# Program-Counter.net
KiCad netlist of a schematic drawn in EAGLE
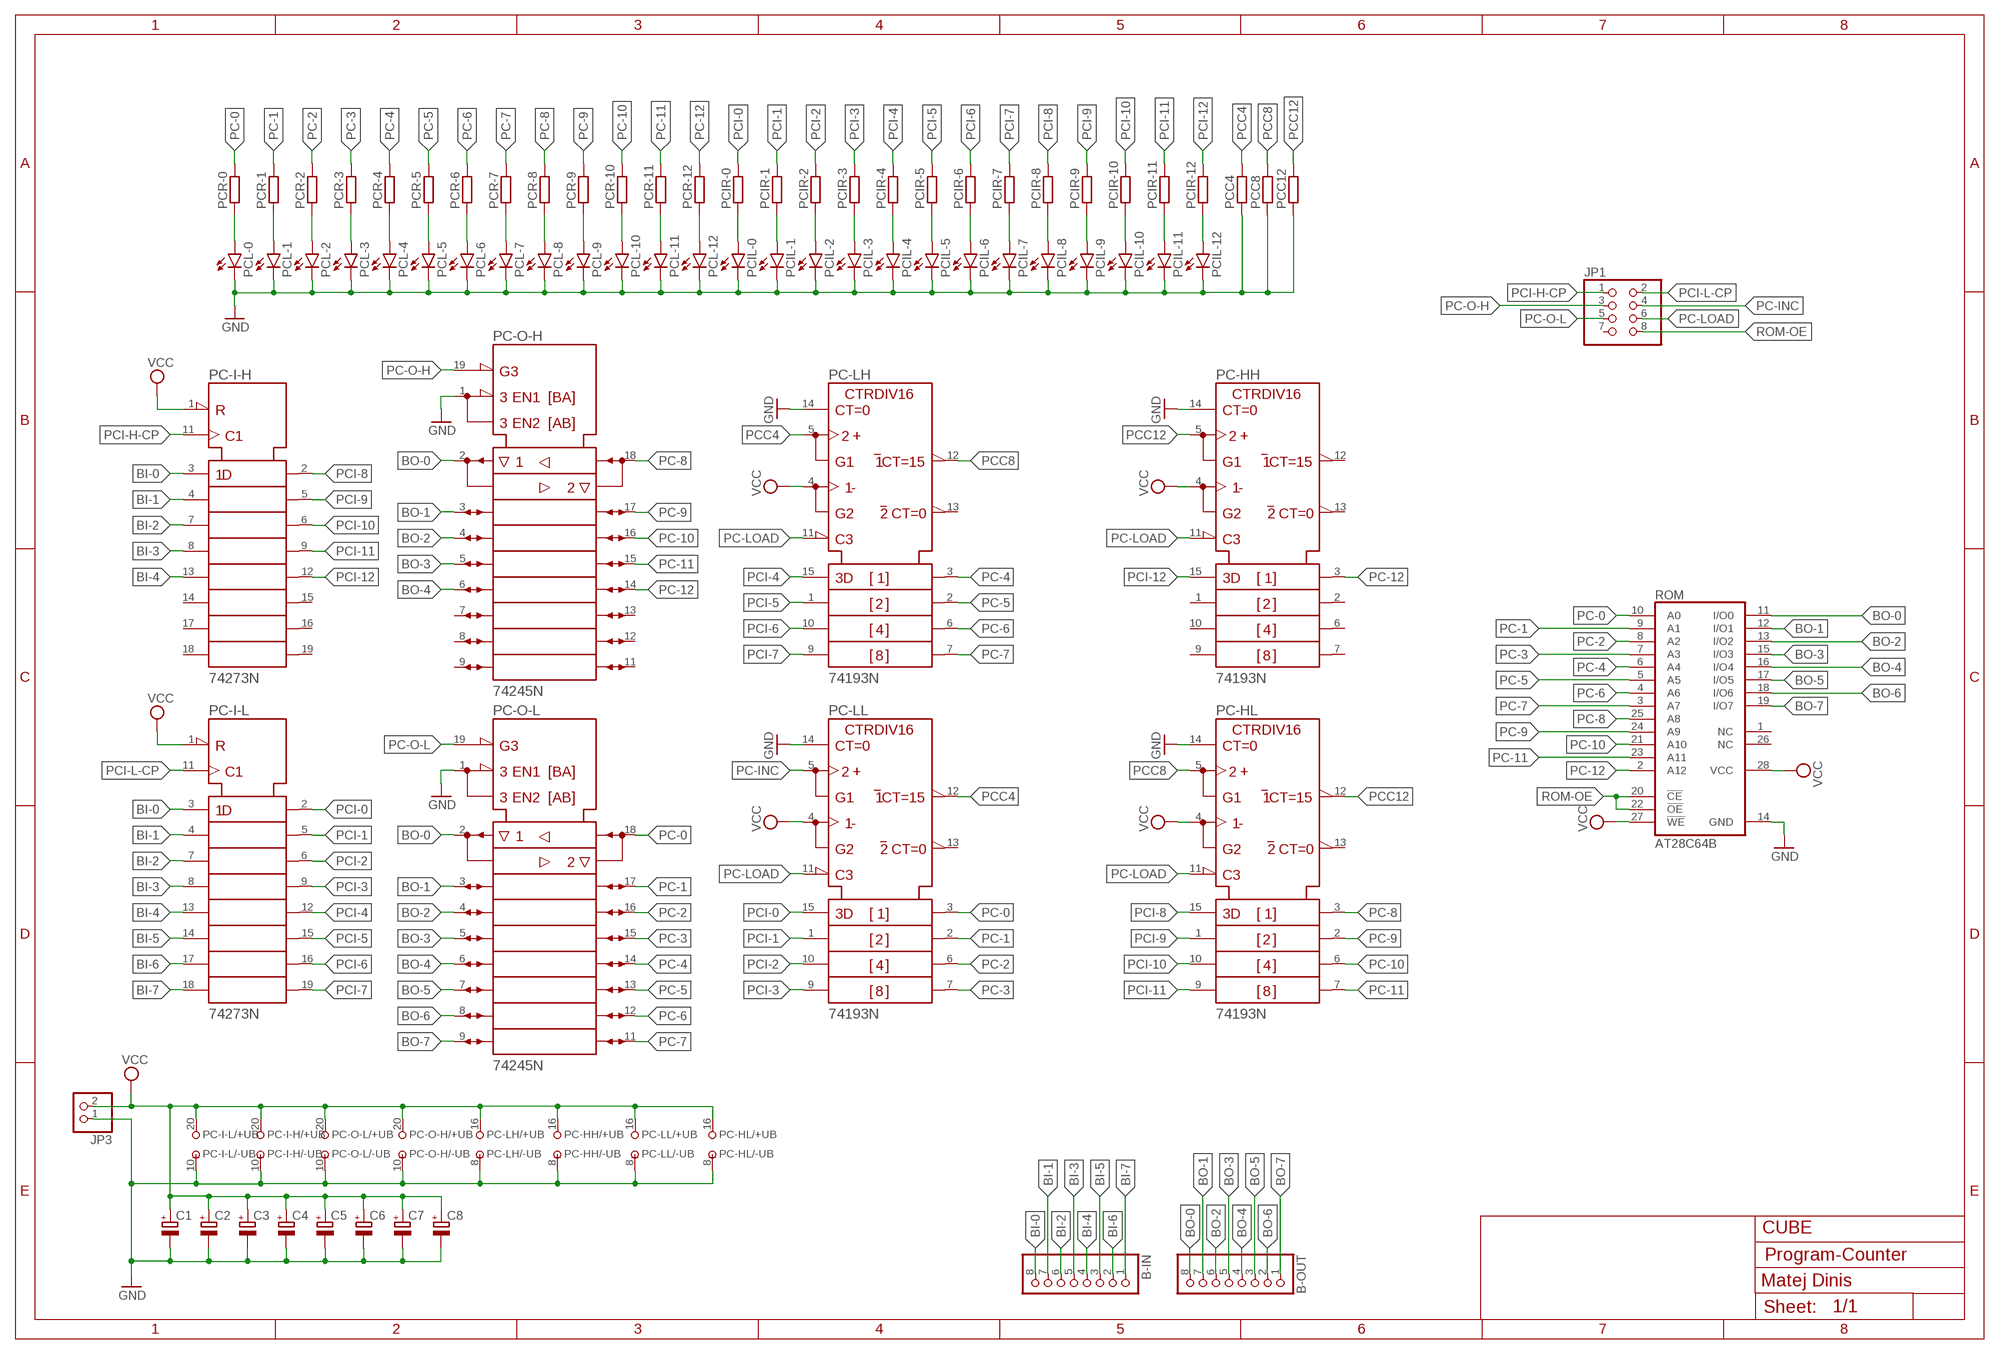
[diagram p0: schematic, sheet 1]

(export (version "E")
  (design (tool "Eeschema 10.0.6"))
  (components
    (comp (ref "B-IN")
      (value "PINHD-1X8")
      (footprint "eagle-import:1X08")
      (libsource (lib "eagle-import") (part "PINHD-1X8"))
    )
    (comp (ref "B-OUT")
      (value "PINHD-1X8")
      (footprint "eagle-import:1X08")
      (libsource (lib "eagle-import") (part "PINHD-1X8"))
    )
    (comp (ref "C1")
      (value "CPOL-EUE3.5-8")
      (footprint "eagle-import:E3,5-8")
      (libsource (lib "eagle-import") (part "CPOL-EUE3.5-8"))
    )
    (comp (ref "C2")
      (value "CPOL-EUE3.5-8")
      (footprint "eagle-import:E3,5-8")
      (libsource (lib "eagle-import") (part "CPOL-EUE3.5-8"))
    )
    (comp (ref "C3")
      (value "CPOL-EUE3.5-8")
      (footprint "eagle-import:E3,5-8")
      (libsource (lib "eagle-import") (part "CPOL-EUE3.5-8"))
    )
    (comp (ref "C4")
      (value "CPOL-EUE3.5-8")
      (footprint "eagle-import:E3,5-8")
      (libsource (lib "eagle-import") (part "CPOL-EUE3.5-8"))
    )
    (comp (ref "C5")
      (value "CPOL-EUE3.5-8")
      (footprint "eagle-import:E3,5-8")
      (libsource (lib "eagle-import") (part "CPOL-EUE3.5-8"))
    )
    (comp (ref "C6")
      (value "CPOL-EUE3.5-8")
      (footprint "eagle-import:E3,5-8")
      (libsource (lib "eagle-import") (part "CPOL-EUE3.5-8"))
    )
    (comp (ref "C7")
      (value "CPOL-EUE3.5-8")
      (footprint "eagle-import:E3,5-8")
      (libsource (lib "eagle-import") (part "CPOL-EUE3.5-8"))
    )
    (comp (ref "C8")
      (value "CPOL-EUE3.5-8")
      (footprint "eagle-import:E3,5-8")
      (libsource (lib "eagle-import") (part "CPOL-EUE3.5-8"))
    )
    (comp (ref "JP1")
      (value "PINHD-2X4")
      (footprint "eagle-import:2X04")
      (libsource (lib "eagle-import") (part "PINHD-2X4"))
    )
    (comp (ref "JP3")
      (value "PINHD-1X2")
      (footprint "eagle-import:1X02")
      (libsource (lib "eagle-import") (part "PINHD-1X2"))
    )
    (comp (ref "PC-HH")
      (value "74193N")
      (footprint "eagle-import:DIL16")
      (libsource (lib "eagle-import") (part "74193N"))
    )
    (comp (ref "PC-HL")
      (value "74193N")
      (footprint "eagle-import:DIL16")
      (libsource (lib "eagle-import") (part "74193N"))
    )
    (comp (ref "PC-I-H")
      (value "74273N")
      (footprint "eagle-import:DIL20")
      (libsource (lib "eagle-import") (part "74273N"))
    )
    (comp (ref "PC-I-L")
      (value "74273N")
      (footprint "eagle-import:DIL20")
      (libsource (lib "eagle-import") (part "74273N"))
    )
    (comp (ref "PC-LH")
      (value "74193N")
      (footprint "eagle-import:DIL16")
      (libsource (lib "eagle-import") (part "74193N"))
    )
    (comp (ref "PC-LL")
      (value "74193N")
      (footprint "eagle-import:DIL16")
      (libsource (lib "eagle-import") (part "74193N"))
    )
    (comp (ref "PC-O-H")
      (value "74245N")
      (footprint "eagle-import:DIL20")
      (libsource (lib "eagle-import") (part "74245N"))
    )
    (comp (ref "PC-O-L")
      (value "74245N")
      (footprint "eagle-import:DIL20")
      (libsource (lib "eagle-import") (part "74245N"))
    )
    (comp (ref "PCC4")
      (value "R-EU_0207/10")
      (footprint "eagle-import:0207_10")
      (libsource (lib "eagle-import") (part "R-EU_0207/10"))
    )
    (comp (ref "PCC8")
      (value "R-EU_0207/10")
      (footprint "eagle-import:0207_10")
      (libsource (lib "eagle-import") (part "R-EU_0207/10"))
    )
    (comp (ref "PCC12")
      (value "R-EU_0207/10")
      (footprint "eagle-import:0207_10")
      (libsource (lib "eagle-import") (part "R-EU_0207/10"))
    )
    (comp (ref "PCIL-0")
      (value "LED5MM")
      (footprint "eagle-import:LED5MM")
      (libsource (lib "eagle-import") (part "LED5MM"))
    )
    (comp (ref "PCIL-1")
      (value "LED5MM")
      (footprint "eagle-import:LED5MM")
      (libsource (lib "eagle-import") (part "LED5MM"))
    )
    (comp (ref "PCIL-2")
      (value "LED5MM")
      (footprint "eagle-import:LED5MM")
      (libsource (lib "eagle-import") (part "LED5MM"))
    )
    (comp (ref "PCIL-3")
      (value "LED5MM")
      (footprint "eagle-import:LED5MM")
      (libsource (lib "eagle-import") (part "LED5MM"))
    )
    (comp (ref "PCIL-4")
      (value "LED5MM")
      (footprint "eagle-import:LED5MM")
      (libsource (lib "eagle-import") (part "LED5MM"))
    )
    (comp (ref "PCIL-5")
      (value "LED5MM")
      (footprint "eagle-import:LED5MM")
      (libsource (lib "eagle-import") (part "LED5MM"))
    )
    (comp (ref "PCIL-6")
      (value "LED5MM")
      (footprint "eagle-import:LED5MM")
      (libsource (lib "eagle-import") (part "LED5MM"))
    )
    (comp (ref "PCIL-7")
      (value "LED5MM")
      (footprint "eagle-import:LED5MM")
      (libsource (lib "eagle-import") (part "LED5MM"))
    )
    (comp (ref "PCIL-8")
      (value "LED5MM")
      (footprint "eagle-import:LED5MM")
      (libsource (lib "eagle-import") (part "LED5MM"))
    )
    (comp (ref "PCIL-9")
      (value "LED5MM")
      (footprint "eagle-import:LED5MM")
      (libsource (lib "eagle-import") (part "LED5MM"))
    )
    (comp (ref "PCIL-10")
      (value "LED5MM")
      (footprint "eagle-import:LED5MM")
      (libsource (lib "eagle-import") (part "LED5MM"))
    )
    (comp (ref "PCIL-11")
      (value "LED5MM")
      (footprint "eagle-import:LED5MM")
      (libsource (lib "eagle-import") (part "LED5MM"))
    )
    (comp (ref "PCIL-12")
      (value "LED5MM")
      (footprint "eagle-import:LED5MM")
      (libsource (lib "eagle-import") (part "LED5MM"))
    )
    (comp (ref "PCIR-0")
      (value "R-EU_0207/10")
      (footprint "eagle-import:0207_10")
      (libsource (lib "eagle-import") (part "R-EU_0207/10"))
    )
    (comp (ref "PCIR-1")
      (value "R-EU_0207/10")
      (footprint "eagle-import:0207_10")
      (libsource (lib "eagle-import") (part "R-EU_0207/10"))
    )
    (comp (ref "PCIR-2")
      (value "R-EU_0207/10")
      (footprint "eagle-import:0207_10")
      (libsource (lib "eagle-import") (part "R-EU_0207/10"))
    )
    (comp (ref "PCIR-3")
      (value "R-EU_0207/10")
      (footprint "eagle-import:0207_10")
      (libsource (lib "eagle-import") (part "R-EU_0207/10"))
    )
    (comp (ref "PCIR-4")
      (value "R-EU_0207/10")
      (footprint "eagle-import:0207_10")
      (libsource (lib "eagle-import") (part "R-EU_0207/10"))
    )
    (comp (ref "PCIR-5")
      (value "R-EU_0207/10")
      (footprint "eagle-import:0207_10")
      (libsource (lib "eagle-import") (part "R-EU_0207/10"))
    )
    (comp (ref "PCIR-6")
      (value "R-EU_0207/10")
      (footprint "eagle-import:0207_10")
      (libsource (lib "eagle-import") (part "R-EU_0207/10"))
    )
    (comp (ref "PCIR-7")
      (value "R-EU_0207/10")
      (footprint "eagle-import:0207_10")
      (libsource (lib "eagle-import") (part "R-EU_0207/10"))
    )
    (comp (ref "PCIR-8")
      (value "R-EU_0207/10")
      (footprint "eagle-import:0207_10")
      (libsource (lib "eagle-import") (part "R-EU_0207/10"))
    )
    (comp (ref "PCIR-9")
      (value "R-EU_0207/10")
      (footprint "eagle-import:0207_10")
      (libsource (lib "eagle-import") (part "R-EU_0207/10"))
    )
    (comp (ref "PCIR-10")
      (value "R-EU_0207/10")
      (footprint "eagle-import:0207_10")
      (libsource (lib "eagle-import") (part "R-EU_0207/10"))
    )
    (comp (ref "PCIR-11")
      (value "R-EU_0207/10")
      (footprint "eagle-import:0207_10")
      (libsource (lib "eagle-import") (part "R-EU_0207/10"))
    )
    (comp (ref "PCIR-12")
      (value "R-EU_0207/10")
      (footprint "eagle-import:0207_10")
      (libsource (lib "eagle-import") (part "R-EU_0207/10"))
    )
    (comp (ref "PCL-0")
      (value "LED5MM")
      (footprint "eagle-import:LED5MM")
      (libsource (lib "eagle-import") (part "LED5MM"))
    )
    (comp (ref "PCL-1")
      (value "LED5MM")
      (footprint "eagle-import:LED5MM")
      (libsource (lib "eagle-import") (part "LED5MM"))
    )
    (comp (ref "PCL-2")
      (value "LED5MM")
      (footprint "eagle-import:LED5MM")
      (libsource (lib "eagle-import") (part "LED5MM"))
    )
    (comp (ref "PCL-3")
      (value "LED5MM")
      (footprint "eagle-import:LED5MM")
      (libsource (lib "eagle-import") (part "LED5MM"))
    )
    (comp (ref "PCL-4")
      (value "LED5MM")
      (footprint "eagle-import:LED5MM")
      (libsource (lib "eagle-import") (part "LED5MM"))
    )
    (comp (ref "PCL-5")
      (value "LED5MM")
      (footprint "eagle-import:LED5MM")
      (libsource (lib "eagle-import") (part "LED5MM"))
    )
    (comp (ref "PCL-6")
      (value "LED5MM")
      (footprint "eagle-import:LED5MM")
      (libsource (lib "eagle-import") (part "LED5MM"))
    )
    (comp (ref "PCL-7")
      (value "LED5MM")
      (footprint "eagle-import:LED5MM")
      (libsource (lib "eagle-import") (part "LED5MM"))
    )
    (comp (ref "PCL-8")
      (value "LED5MM")
      (footprint "eagle-import:LED5MM")
      (libsource (lib "eagle-import") (part "LED5MM"))
    )
    (comp (ref "PCL-9")
      (value "LED5MM")
      (footprint "eagle-import:LED5MM")
      (libsource (lib "eagle-import") (part "LED5MM"))
    )
    (comp (ref "PCL-10")
      (value "LED5MM")
      (footprint "eagle-import:LED5MM")
      (libsource (lib "eagle-import") (part "LED5MM"))
    )
    (comp (ref "PCL-11")
      (value "LED5MM")
      (footprint "eagle-import:LED5MM")
      (libsource (lib "eagle-import") (part "LED5MM"))
    )
    (comp (ref "PCL-12")
      (value "LED5MM")
      (footprint "eagle-import:LED5MM")
      (libsource (lib "eagle-import") (part "LED5MM"))
    )
    (comp (ref "PCR-0")
      (value "R-EU_0207/10")
      (footprint "eagle-import:0207_10")
      (libsource (lib "eagle-import") (part "R-EU_0207/10"))
    )
    (comp (ref "PCR-1")
      (value "R-EU_0207/10")
      (footprint "eagle-import:0207_10")
      (libsource (lib "eagle-import") (part "R-EU_0207/10"))
    )
    (comp (ref "PCR-2")
      (value "R-EU_0207/10")
      (footprint "eagle-import:0207_10")
      (libsource (lib "eagle-import") (part "R-EU_0207/10"))
    )
    (comp (ref "PCR-3")
      (value "R-EU_0207/10")
      (footprint "eagle-import:0207_10")
      (libsource (lib "eagle-import") (part "R-EU_0207/10"))
    )
    (comp (ref "PCR-4")
      (value "R-EU_0207/10")
      (footprint "eagle-import:0207_10")
      (libsource (lib "eagle-import") (part "R-EU_0207/10"))
    )
    (comp (ref "PCR-5")
      (value "R-EU_0207/10")
      (footprint "eagle-import:0207_10")
      (libsource (lib "eagle-import") (part "R-EU_0207/10"))
    )
    (comp (ref "PCR-6")
      (value "R-EU_0207/10")
      (footprint "eagle-import:0207_10")
      (libsource (lib "eagle-import") (part "R-EU_0207/10"))
    )
    (comp (ref "PCR-7")
      (value "R-EU_0207/10")
      (footprint "eagle-import:0207_10")
      (libsource (lib "eagle-import") (part "R-EU_0207/10"))
    )
    (comp (ref "PCR-8")
      (value "R-EU_0207/10")
      (footprint "eagle-import:0207_10")
      (libsource (lib "eagle-import") (part "R-EU_0207/10"))
    )
    (comp (ref "PCR-9")
      (value "R-EU_0207/10")
      (footprint "eagle-import:0207_10")
      (libsource (lib "eagle-import") (part "R-EU_0207/10"))
    )
    (comp (ref "PCR-10")
      (value "R-EU_0207/10")
      (footprint "eagle-import:0207_10")
      (libsource (lib "eagle-import") (part "R-EU_0207/10"))
    )
    (comp (ref "PCR-11")
      (value "R-EU_0207/10")
      (footprint "eagle-import:0207_10")
      (libsource (lib "eagle-import") (part "R-EU_0207/10"))
    )
    (comp (ref "PCR-12")
      (value "R-EU_0207/10")
      (footprint "eagle-import:0207_10")
      (libsource (lib "eagle-import") (part "R-EU_0207/10"))
    )
    (comp (ref "ROM")
      (value "AT28C64B")
      (footprint "eagle-import:DIL28-6")
      (fields (field (name "MPN") "AT28C64B-15PU"))
      (libsource (lib "eagle-import") (part "28C64C"))
    )
  )
  (nets
    (net (code "1") (name "BI-0") (class "Default")
      (node (ref "B-IN") (pin "8") (pinfunction "8_8") (pintype "passive"))
      (node (ref "PC-I-H") (pin "3") (pinfunction "1D_3") (pintype "input"))
      (node (ref "PC-I-L") (pin "3") (pinfunction "1D_3") (pintype "input"))
    )
    (net (code "2") (name "BI-1") (class "Default")
      (node (ref "B-IN") (pin "7") (pinfunction "7_7") (pintype "passive"))
      (node (ref "PC-I-H") (pin "4") (pinfunction "2D_4") (pintype "input"))
      (node (ref "PC-I-L") (pin "4") (pinfunction "2D_4") (pintype "input"))
    )
    (net (code "3") (name "BI-2") (class "Default")
      (node (ref "B-IN") (pin "6") (pinfunction "6_6") (pintype "passive"))
      (node (ref "PC-I-H") (pin "7") (pinfunction "3D_7") (pintype "input"))
      (node (ref "PC-I-L") (pin "7") (pinfunction "3D_7") (pintype "input"))
    )
    (net (code "4") (name "BI-3") (class "Default")
      (node (ref "B-IN") (pin "5") (pinfunction "5_5") (pintype "passive"))
      (node (ref "PC-I-H") (pin "8") (pinfunction "4D_8") (pintype "input"))
      (node (ref "PC-I-L") (pin "8") (pinfunction "4D_8") (pintype "input"))
    )
    (net (code "5") (name "BI-4") (class "Default")
      (node (ref "B-IN") (pin "4") (pinfunction "4_4") (pintype "passive"))
      (node (ref "PC-I-H") (pin "13") (pinfunction "5D_13") (pintype "input"))
      (node (ref "PC-I-L") (pin "13") (pinfunction "5D_13") (pintype "input"))
    )
    (net (code "6") (name "BI-5") (class "Default")
      (node (ref "B-IN") (pin "3") (pinfunction "3_3") (pintype "passive"))
      (node (ref "PC-I-L") (pin "14") (pinfunction "6D_14") (pintype "input"))
    )
    (net (code "7") (name "BI-6") (class "Default")
      (node (ref "B-IN") (pin "2") (pinfunction "2_2") (pintype "passive"))
      (node (ref "PC-I-L") (pin "17") (pinfunction "7D_17") (pintype "input"))
    )
    (net (code "8") (name "BI-7") (class "Default")
      (node (ref "B-IN") (pin "1") (pinfunction "1_1") (pintype "passive"))
      (node (ref "PC-I-L") (pin "18") (pinfunction "8D_18") (pintype "input"))
    )
    (net (code "9") (name "BO-0") (class "Default")
      (node (ref "B-OUT") (pin "8") (pinfunction "8_8") (pintype "passive"))
      (node (ref "PC-O-H") (pin "2") (pinfunction "A1_2") (pintype "bidirectional"))
      (node (ref "PC-O-L") (pin "2") (pinfunction "A1_2") (pintype "bidirectional"))
      (node (ref "ROM") (pin "11") (pinfunction "I/O0_11") (pintype "bidirectional"))
    )
    (net (code "10") (name "BO-1") (class "Default")
      (node (ref "B-OUT") (pin "7") (pinfunction "7_7") (pintype "passive"))
      (node (ref "PC-O-H") (pin "3") (pinfunction "A2_3") (pintype "bidirectional"))
      (node (ref "PC-O-L") (pin "3") (pinfunction "A2_3") (pintype "bidirectional"))
      (node (ref "ROM") (pin "12") (pinfunction "I/O1_12") (pintype "bidirectional"))
    )
    (net (code "11") (name "BO-2") (class "Default")
      (node (ref "B-OUT") (pin "6") (pinfunction "6_6") (pintype "passive"))
      (node (ref "PC-O-H") (pin "4") (pinfunction "A3_4") (pintype "bidirectional"))
      (node (ref "PC-O-L") (pin "4") (pinfunction "A3_4") (pintype "bidirectional"))
      (node (ref "ROM") (pin "13") (pinfunction "I/O2_13") (pintype "bidirectional"))
    )
    (net (code "12") (name "BO-3") (class "Default")
      (node (ref "B-OUT") (pin "5") (pinfunction "5_5") (pintype "passive"))
      (node (ref "PC-O-H") (pin "5") (pinfunction "A4_5") (pintype "bidirectional"))
      (node (ref "PC-O-L") (pin "5") (pinfunction "A4_5") (pintype "bidirectional"))
      (node (ref "ROM") (pin "15") (pinfunction "I/O3_15") (pintype "bidirectional"))
    )
    (net (code "13") (name "BO-4") (class "Default")
      (node (ref "B-OUT") (pin "4") (pinfunction "4_4") (pintype "passive"))
      (node (ref "PC-O-H") (pin "6") (pinfunction "A5_6") (pintype "bidirectional"))
      (node (ref "PC-O-L") (pin "6") (pinfunction "A5_6") (pintype "bidirectional"))
      (node (ref "ROM") (pin "16") (pinfunction "I/O4_16") (pintype "bidirectional"))
    )
    (net (code "14") (name "BO-5") (class "Default")
      (node (ref "B-OUT") (pin "3") (pinfunction "3_3") (pintype "passive"))
      (node (ref "PC-O-L") (pin "7") (pinfunction "A6_7") (pintype "bidirectional"))
      (node (ref "ROM") (pin "17") (pinfunction "I/O5_17") (pintype "bidirectional"))
    )
    (net (code "15") (name "BO-6") (class "Default")
      (node (ref "B-OUT") (pin "2") (pinfunction "2_2") (pintype "passive"))
      (node (ref "PC-O-L") (pin "8") (pinfunction "A7_8") (pintype "bidirectional"))
      (node (ref "ROM") (pin "18") (pinfunction "I/O6_18") (pintype "bidirectional"))
    )
    (net (code "16") (name "BO-7") (class "Default")
      (node (ref "B-OUT") (pin "1") (pinfunction "1_1") (pintype "passive"))
      (node (ref "PC-O-L") (pin "9") (pinfunction "A8_9") (pintype "bidirectional"))
      (node (ref "ROM") (pin "19") (pinfunction "I/O7_19") (pintype "bidirectional"))
    )
    (net (code "17") (name "GND") (class "Default")
      (node (ref "C1") (pin "-") (pinfunction "-_-") (pintype "passive"))
      (node (ref "C2") (pin "-") (pinfunction "-_-") (pintype "passive"))
      (node (ref "C3") (pin "-") (pinfunction "-_-") (pintype "passive"))
      (node (ref "C4") (pin "-") (pinfunction "-_-") (pintype "passive"))
      (node (ref "C5") (pin "-") (pinfunction "-_-") (pintype "passive"))
      (node (ref "C6") (pin "-") (pinfunction "-_-") (pintype "passive"))
      (node (ref "C7") (pin "-") (pinfunction "-_-") (pintype "passive"))
      (node (ref "C8") (pin "-") (pinfunction "-_-") (pintype "passive"))
      (node (ref "JP3") (pin "1") (pinfunction "1_1") (pintype "passive"))
      (node (ref "PC-HH") (pin "14") (pinfunction "CLR_14") (pintype "input"))
      (node (ref "PC-HH") (pin "8") (pinfunction "-UB_8") (pintype "power_in"))
      (node (ref "PC-HL") (pin "14") (pinfunction "CLR_14") (pintype "input"))
      (node (ref "PC-HL") (pin "8") (pinfunction "-UB_8") (pintype "power_in"))
      (node (ref "PC-I-H") (pin "10") (pinfunction "-UB_10") (pintype "power_in"))
      (node (ref "PC-I-L") (pin "10") (pinfunction "-UB_10") (pintype "power_in"))
      (node (ref "PC-LH") (pin "14") (pinfunction "CLR_14") (pintype "input"))
      (node (ref "PC-LH") (pin "8") (pinfunction "-UB_8") (pintype "power_in"))
      (node (ref "PC-LL") (pin "14") (pinfunction "CLR_14") (pintype "input"))
      (node (ref "PC-LL") (pin "8") (pinfunction "-UB_8") (pintype "power_in"))
      (node (ref "PC-O-H") (pin "1") (pinfunction "DIR_1") (pintype "input"))
      (node (ref "PC-O-H") (pin "10") (pinfunction "-UB_10") (pintype "power_in"))
      (node (ref "PC-O-L") (pin "1") (pinfunction "DIR_1") (pintype "input"))
      (node (ref "PC-O-L") (pin "10") (pinfunction "-UB_10") (pintype "power_in"))
      (node (ref "PCC12") (pin "1") (pinfunction "1_1") (pintype "passive"))
      (node (ref "PCC4") (pin "1") (pinfunction "1_1") (pintype "passive"))
      (node (ref "PCC8") (pin "1") (pinfunction "1_1") (pintype "passive"))
      (node (ref "PCIL-0") (pin "K") (pinfunction "C_K") (pintype "passive"))
      (node (ref "PCIL-1") (pin "K") (pinfunction "C_K") (pintype "passive"))
      (node (ref "PCIL-10") (pin "K") (pinfunction "C_K") (pintype "passive"))
      (node (ref "PCIL-11") (pin "K") (pinfunction "C_K") (pintype "passive"))
      (node (ref "PCIL-12") (pin "K") (pinfunction "C_K") (pintype "passive"))
      (node (ref "PCIL-2") (pin "K") (pinfunction "C_K") (pintype "passive"))
      (node (ref "PCIL-3") (pin "K") (pinfunction "C_K") (pintype "passive"))
      (node (ref "PCIL-4") (pin "K") (pinfunction "C_K") (pintype "passive"))
      (node (ref "PCIL-5") (pin "K") (pinfunction "C_K") (pintype "passive"))
      (node (ref "PCIL-6") (pin "K") (pinfunction "C_K") (pintype "passive"))
      (node (ref "PCIL-7") (pin "K") (pinfunction "C_K") (pintype "passive"))
      (node (ref "PCIL-8") (pin "K") (pinfunction "C_K") (pintype "passive"))
      (node (ref "PCIL-9") (pin "K") (pinfunction "C_K") (pintype "passive"))
      (node (ref "PCL-0") (pin "K") (pinfunction "C_K") (pintype "passive"))
      (node (ref "PCL-1") (pin "K") (pinfunction "C_K") (pintype "passive"))
      (node (ref "PCL-10") (pin "K") (pinfunction "C_K") (pintype "passive"))
      (node (ref "PCL-11") (pin "K") (pinfunction "C_K") (pintype "passive"))
      (node (ref "PCL-12") (pin "K") (pinfunction "C_K") (pintype "passive"))
      (node (ref "PCL-2") (pin "K") (pinfunction "C_K") (pintype "passive"))
      (node (ref "PCL-3") (pin "K") (pinfunction "C_K") (pintype "passive"))
      (node (ref "PCL-4") (pin "K") (pinfunction "C_K") (pintype "passive"))
      (node (ref "PCL-5") (pin "K") (pinfunction "C_K") (pintype "passive"))
      (node (ref "PCL-6") (pin "K") (pinfunction "C_K") (pintype "passive"))
      (node (ref "PCL-7") (pin "K") (pinfunction "C_K") (pintype "passive"))
      (node (ref "PCL-8") (pin "K") (pinfunction "C_K") (pintype "passive"))
      (node (ref "PCL-9") (pin "K") (pinfunction "C_K") (pintype "passive"))
      (node (ref "ROM") (pin "14") (pinfunction "GND_14") (pintype "power_in"))
    )
    (net (code "18") (name "Net-(PCIL-0-PadA)") (class "Default")
      (node (ref "PCIL-0") (pin "A") (pinfunction "A_A") (pintype "passive"))
      (node (ref "PCIR-0") (pin "1") (pinfunction "1_1") (pintype "passive"))
    )
    (net (code "19") (name "Net-(PCIL-1-PadA)") (class "Default")
      (node (ref "PCIL-1") (pin "A") (pinfunction "A_A") (pintype "passive"))
      (node (ref "PCIR-1") (pin "1") (pinfunction "1_1") (pintype "passive"))
    )
    (net (code "20") (name "Net-(PCIL-2-PadA)") (class "Default")
      (node (ref "PCIL-2") (pin "A") (pinfunction "A_A") (pintype "passive"))
      (node (ref "PCIR-2") (pin "1") (pinfunction "1_1") (pintype "passive"))
    )
    (net (code "21") (name "Net-(PCIL-3-PadA)") (class "Default")
      (node (ref "PCIL-3") (pin "A") (pinfunction "A_A") (pintype "passive"))
      (node (ref "PCIR-3") (pin "1") (pinfunction "1_1") (pintype "passive"))
    )
    (net (code "22") (name "Net-(PCIL-4-PadA)") (class "Default")
      (node (ref "PCIL-4") (pin "A") (pinfunction "A_A") (pintype "passive"))
      (node (ref "PCIR-4") (pin "1") (pinfunction "1_1") (pintype "passive"))
    )
    (net (code "23") (name "Net-(PCIL-5-PadA)") (class "Default")
      (node (ref "PCIL-5") (pin "A") (pinfunction "A_A") (pintype "passive"))
      (node (ref "PCIR-5") (pin "1") (pinfunction "1_1") (pintype "passive"))
    )
    (net (code "24") (name "Net-(PCIL-6-PadA)") (class "Default")
      (node (ref "PCIL-6") (pin "A") (pinfunction "A_A") (pintype "passive"))
      (node (ref "PCIR-6") (pin "1") (pinfunction "1_1") (pintype "passive"))
    )
    (net (code "25") (name "Net-(PCIL-7-PadA)") (class "Default")
      (node (ref "PCIL-7") (pin "A") (pinfunction "A_A") (pintype "passive"))
      (node (ref "PCIR-7") (pin "1") (pinfunction "1_1") (pintype "passive"))
    )
    (net (code "26") (name "Net-(PCIL-8-PadA)") (class "Default")
      (node (ref "PCIL-8") (pin "A") (pinfunction "A_A") (pintype "passive"))
      (node (ref "PCIR-8") (pin "1") (pinfunction "1_1") (pintype "passive"))
    )
    (net (code "27") (name "Net-(PCIL-9-PadA)") (class "Default")
      (node (ref "PCIL-9") (pin "A") (pinfunction "A_A") (pintype "passive"))
      (node (ref "PCIR-9") (pin "1") (pinfunction "1_1") (pintype "passive"))
    )
    (net (code "28") (name "Net-(PCIL-10-PadA)") (class "Default")
      (node (ref "PCIL-10") (pin "A") (pinfunction "A_A") (pintype "passive"))
      (node (ref "PCIR-10") (pin "1") (pinfunction "1_1") (pintype "passive"))
    )
    (net (code "29") (name "Net-(PCIL-11-PadA)") (class "Default")
      (node (ref "PCIL-11") (pin "A") (pinfunction "A_A") (pintype "passive"))
      (node (ref "PCIR-11") (pin "1") (pinfunction "1_1") (pintype "passive"))
    )
    (net (code "30") (name "Net-(PCIL-12-PadA)") (class "Default")
      (node (ref "PCIL-12") (pin "A") (pinfunction "A_A") (pintype "passive"))
      (node (ref "PCIR-12") (pin "1") (pinfunction "1_1") (pintype "passive"))
    )
    (net (code "31") (name "Net-(PCL-0-PadA)") (class "Default")
      (node (ref "PCL-0") (pin "A") (pinfunction "A_A") (pintype "passive"))
      (node (ref "PCR-0") (pin "1") (pinfunction "1_1") (pintype "passive"))
    )
    (net (code "32") (name "Net-(PCL-1-PadA)") (class "Default")
      (node (ref "PCL-1") (pin "A") (pinfunction "A_A") (pintype "passive"))
      (node (ref "PCR-1") (pin "1") (pinfunction "1_1") (pintype "passive"))
    )
    (net (code "33") (name "Net-(PCL-2-PadA)") (class "Default")
      (node (ref "PCL-2") (pin "A") (pinfunction "A_A") (pintype "passive"))
      (node (ref "PCR-2") (pin "1") (pinfunction "1_1") (pintype "passive"))
    )
    (net (code "34") (name "Net-(PCL-3-PadA)") (class "Default")
      (node (ref "PCL-3") (pin "A") (pinfunction "A_A") (pintype "passive"))
      (node (ref "PCR-3") (pin "1") (pinfunction "1_1") (pintype "passive"))
    )
    (net (code "35") (name "Net-(PCL-4-PadA)") (class "Default")
      (node (ref "PCL-4") (pin "A") (pinfunction "A_A") (pintype "passive"))
      (node (ref "PCR-4") (pin "1") (pinfunction "1_1") (pintype "passive"))
    )
    (net (code "36") (name "Net-(PCL-5-PadA)") (class "Default")
      (node (ref "PCL-5") (pin "A") (pinfunction "A_A") (pintype "passive"))
      (node (ref "PCR-5") (pin "1") (pinfunction "1_1") (pintype "passive"))
    )
    (net (code "37") (name "Net-(PCL-6-PadA)") (class "Default")
      (node (ref "PCL-6") (pin "A") (pinfunction "A_A") (pintype "passive"))
      (node (ref "PCR-6") (pin "1") (pinfunction "1_1") (pintype "passive"))
    )
    (net (code "38") (name "Net-(PCL-7-PadA)") (class "Default")
      (node (ref "PCL-7") (pin "A") (pinfunction "A_A") (pintype "passive"))
      (node (ref "PCR-7") (pin "1") (pinfunction "1_1") (pintype "passive"))
    )
    (net (code "39") (name "Net-(PCL-8-PadA)") (class "Default")
      (node (ref "PCL-8") (pin "A") (pinfunction "A_A") (pintype "passive"))
      (node (ref "PCR-8") (pin "1") (pinfunction "1_1") (pintype "passive"))
    )
    (net (code "40") (name "Net-(PCL-9-PadA)") (class "Default")
      (node (ref "PCL-9") (pin "A") (pinfunction "A_A") (pintype "passive"))
      (node (ref "PCR-9") (pin "1") (pinfunction "1_1") (pintype "passive"))
    )
    (net (code "41") (name "Net-(PCL-10-PadA)") (class "Default")
      (node (ref "PCL-10") (pin "A") (pinfunction "A_A") (pintype "passive"))
      (node (ref "PCR-10") (pin "1") (pinfunction "1_1") (pintype "passive"))
    )
    (net (code "42") (name "Net-(PCL-11-PadA)") (class "Default")
      (node (ref "PCL-11") (pin "A") (pinfunction "A_A") (pintype "passive"))
      (node (ref "PCR-11") (pin "1") (pinfunction "1_1") (pintype "passive"))
    )
    (net (code "43") (name "Net-(PCL-12-PadA)") (class "Default")
      (node (ref "PCL-12") (pin "A") (pinfunction "A_A") (pintype "passive"))
      (node (ref "PCR-12") (pin "1") (pinfunction "1_1") (pintype "passive"))
    )
    (net (code "44") (name "PC-0") (class "Default")
      (node (ref "PC-LL") (pin "3") (pinfunction "QA_3") (pintype "output"))
      (node (ref "PC-O-L") (pin "18") (pinfunction "B1_18") (pintype "bidirectional"))
      (node (ref "PCR-0") (pin "2") (pinfunction "2_2") (pintype "passive"))
      (node (ref "ROM") (pin "10") (pinfunction "A0_10") (pintype "input"))
    )
    (net (code "45") (name "PC-1") (class "Default")
      (node (ref "PC-LL") (pin "2") (pinfunction "QB_2") (pintype "output"))
      (node (ref "PC-O-L") (pin "17") (pinfunction "B2_17") (pintype "bidirectional"))
      (node (ref "PCR-1") (pin "2") (pinfunction "2_2") (pintype "passive"))
      (node (ref "ROM") (pin "9") (pinfunction "A1_9") (pintype "input"))
    )
    (net (code "46") (name "PC-2") (class "Default")
      (node (ref "PC-LL") (pin "6") (pinfunction "QC_6") (pintype "output"))
      (node (ref "PC-O-L") (pin "16") (pinfunction "B3_16") (pintype "bidirectional"))
      (node (ref "PCR-2") (pin "2") (pinfunction "2_2") (pintype "passive"))
      (node (ref "ROM") (pin "8") (pinfunction "A2_8") (pintype "input"))
    )
    (net (code "47") (name "PC-3") (class "Default")
      (node (ref "PC-LL") (pin "7") (pinfunction "QD_7") (pintype "output"))
      (node (ref "PC-O-L") (pin "15") (pinfunction "B4_15") (pintype "bidirectional"))
      (node (ref "PCR-3") (pin "2") (pinfunction "2_2") (pintype "passive"))
      (node (ref "ROM") (pin "7") (pinfunction "A3_7") (pintype "input"))
    )
    (net (code "48") (name "PC-4") (class "Default")
      (node (ref "PC-LH") (pin "3") (pinfunction "QA_3") (pintype "output"))
      (node (ref "PC-O-L") (pin "14") (pinfunction "B5_14") (pintype "bidirectional"))
      (node (ref "PCR-4") (pin "2") (pinfunction "2_2") (pintype "passive"))
      (node (ref "ROM") (pin "6") (pinfunction "A4_6") (pintype "input"))
    )
    (net (code "49") (name "PC-5") (class "Default")
      (node (ref "PC-LH") (pin "2") (pinfunction "QB_2") (pintype "output"))
      (node (ref "PC-O-L") (pin "13") (pinfunction "B6_13") (pintype "bidirectional"))
      (node (ref "PCR-5") (pin "2") (pinfunction "2_2") (pintype "passive"))
      (node (ref "ROM") (pin "5") (pinfunction "A5_5") (pintype "input"))
    )
    (net (code "50") (name "PC-6") (class "Default")
      (node (ref "PC-LH") (pin "6") (pinfunction "QC_6") (pintype "output"))
      (node (ref "PC-O-L") (pin "12") (pinfunction "B7_12") (pintype "bidirectional"))
      (node (ref "PCR-6") (pin "2") (pinfunction "2_2") (pintype "passive"))
      (node (ref "ROM") (pin "4") (pinfunction "A6_4") (pintype "input"))
    )
    (net (code "51") (name "PC-7") (class "Default")
      (node (ref "PC-LH") (pin "7") (pinfunction "QD_7") (pintype "output"))
      (node (ref "PC-O-L") (pin "11") (pinfunction "B8_11") (pintype "bidirectional"))
      (node (ref "PCR-7") (pin "2") (pinfunction "2_2") (pintype "passive"))
      (node (ref "ROM") (pin "3") (pinfunction "A7_3") (pintype "input"))
    )
    (net (code "52") (name "PC-8") (class "Default")
      (node (ref "PC-HL") (pin "3") (pinfunction "QA_3") (pintype "output"))
      (node (ref "PC-O-H") (pin "18") (pinfunction "B1_18") (pintype "bidirectional"))
      (node (ref "PCR-8") (pin "2") (pinfunction "2_2") (pintype "passive"))
      (node (ref "ROM") (pin "25") (pinfunction "A8_25") (pintype "input"))
    )
    (net (code "53") (name "PC-9") (class "Default")
      (node (ref "PC-HL") (pin "2") (pinfunction "QB_2") (pintype "output"))
      (node (ref "PC-O-H") (pin "17") (pinfunction "B2_17") (pintype "bidirectional"))
      (node (ref "PCR-9") (pin "2") (pinfunction "2_2") (pintype "passive"))
      (node (ref "ROM") (pin "24") (pinfunction "A9_24") (pintype "input"))
    )
    (net (code "54") (name "PC-10") (class "Default")
      (node (ref "PC-HL") (pin "6") (pinfunction "QC_6") (pintype "output"))
      (node (ref "PC-O-H") (pin "16") (pinfunction "B3_16") (pintype "bidirectional"))
      (node (ref "PCR-10") (pin "2") (pinfunction "2_2") (pintype "passive"))
      (node (ref "ROM") (pin "21") (pinfunction "A10_21") (pintype "input"))
    )
    (net (code "55") (name "PC-11") (class "Default")
      (node (ref "PC-HL") (pin "7") (pinfunction "QD_7") (pintype "output"))
      (node (ref "PC-O-H") (pin "15") (pinfunction "B4_15") (pintype "bidirectional"))
      (node (ref "PCR-11") (pin "2") (pinfunction "2_2") (pintype "passive"))
      (node (ref "ROM") (pin "23") (pinfunction "A11_23") (pintype "input"))
    )
    (net (code "56") (name "PC-12") (class "Default")
      (node (ref "PC-HH") (pin "3") (pinfunction "QA_3") (pintype "output"))
      (node (ref "PC-O-H") (pin "14") (pinfunction "B5_14") (pintype "bidirectional"))
      (node (ref "PCR-12") (pin "2") (pinfunction "2_2") (pintype "passive"))
      (node (ref "ROM") (pin "2") (pinfunction "A12_2") (pintype "input"))
    )
    (net (code "57") (name "PC-INC") (class "Default")
      (node (ref "JP1") (pin "4") (pinfunction "4_4") (pintype "passive"))
      (node (ref "PC-LL") (pin "5") (pinfunction "UP_5") (pintype "input"))
    )
    (net (code "58") (name "PC-LOAD") (class "Default")
      (node (ref "JP1") (pin "6") (pinfunction "6_6") (pintype "passive"))
      (node (ref "PC-HH") (pin "11") (pinfunction "~{LOAD}_11") (pintype "input"))
      (node (ref "PC-HL") (pin "11") (pinfunction "~{LOAD}_11") (pintype "input"))
      (node (ref "PC-LH") (pin "11") (pinfunction "~{LOAD}_11") (pintype "input"))
      (node (ref "PC-LL") (pin "11") (pinfunction "~{LOAD}_11") (pintype "input"))
    )
    (net (code "59") (name "PC-O-H") (class "Default")
      (node (ref "JP1") (pin "3") (pinfunction "3_3") (pintype "passive"))
      (node (ref "PC-O-H") (pin "19") (pinfunction "~{G}_19") (pintype "input"))
    )
    (net (code "60") (name "PC-O-L") (class "Default")
      (node (ref "JP1") (pin "5") (pinfunction "5_5") (pintype "passive"))
      (node (ref "PC-O-L") (pin "19") (pinfunction "~{G}_19") (pintype "input"))
    )
    (net (code "61") (name "PCC4") (class "Default")
      (node (ref "PC-LH") (pin "5") (pinfunction "UP_5") (pintype "input"))
      (node (ref "PC-LL") (pin "12") (pinfunction "~{CO}_12") (pintype "output"))
      (node (ref "PCC4") (pin "2") (pinfunction "2_2") (pintype "passive"))
    )
    (net (code "62") (name "PCC8") (class "Default")
      (node (ref "PC-HL") (pin "5") (pinfunction "UP_5") (pintype "input"))
      (node (ref "PC-LH") (pin "12") (pinfunction "~{CO}_12") (pintype "output"))
      (node (ref "PCC8") (pin "2") (pinfunction "2_2") (pintype "passive"))
    )
    (net (code "63") (name "PCC12") (class "Default")
      (node (ref "PC-HH") (pin "5") (pinfunction "UP_5") (pintype "input"))
      (node (ref "PC-HL") (pin "12") (pinfunction "~{CO}_12") (pintype "output"))
      (node (ref "PCC12") (pin "2") (pinfunction "2_2") (pintype "passive"))
    )
    (net (code "64") (name "PCI-0") (class "Default")
      (node (ref "PC-I-L") (pin "2") (pinfunction "1Q_2") (pintype "output"))
      (node (ref "PC-LL") (pin "15") (pinfunction "A_15") (pintype "input"))
      (node (ref "PCIR-0") (pin "2") (pinfunction "2_2") (pintype "passive"))
    )
    (net (code "65") (name "PCI-1") (class "Default")
      (node (ref "PC-I-L") (pin "5") (pinfunction "2Q_5") (pintype "output"))
      (node (ref "PC-LL") (pin "1") (pinfunction "B_1") (pintype "input"))
      (node (ref "PCIR-1") (pin "2") (pinfunction "2_2") (pintype "passive"))
    )
    (net (code "66") (name "PCI-2") (class "Default")
      (node (ref "PC-I-L") (pin "6") (pinfunction "3Q_6") (pintype "output"))
      (node (ref "PC-LL") (pin "10") (pinfunction "C_10") (pintype "input"))
      (node (ref "PCIR-2") (pin "2") (pinfunction "2_2") (pintype "passive"))
    )
    (net (code "67") (name "PCI-3") (class "Default")
      (node (ref "PC-I-L") (pin "9") (pinfunction "4Q_9") (pintype "output"))
      (node (ref "PC-LL") (pin "9") (pinfunction "D_9") (pintype "input"))
      (node (ref "PCIR-3") (pin "2") (pinfunction "2_2") (pintype "passive"))
    )
    (net (code "68") (name "PCI-4") (class "Default")
      (node (ref "PC-I-L") (pin "12") (pinfunction "5Q_12") (pintype "output"))
      (node (ref "PC-LH") (pin "15") (pinfunction "A_15") (pintype "input"))
      (node (ref "PCIR-4") (pin "2") (pinfunction "2_2") (pintype "passive"))
    )
    (net (code "69") (name "PCI-5") (class "Default")
      (node (ref "PC-I-L") (pin "15") (pinfunction "6Q_15") (pintype "output"))
      (node (ref "PC-LH") (pin "1") (pinfunction "B_1") (pintype "input"))
      (node (ref "PCIR-5") (pin "2") (pinfunction "2_2") (pintype "passive"))
    )
    (net (code "70") (name "PCI-6") (class "Default")
      (node (ref "PC-I-L") (pin "16") (pinfunction "7Q_16") (pintype "output"))
      (node (ref "PC-LH") (pin "10") (pinfunction "C_10") (pintype "input"))
      (node (ref "PCIR-6") (pin "2") (pinfunction "2_2") (pintype "passive"))
    )
    (net (code "71") (name "PCI-7") (class "Default")
      (node (ref "PC-I-L") (pin "19") (pinfunction "8Q_19") (pintype "output"))
      (node (ref "PC-LH") (pin "9") (pinfunction "D_9") (pintype "input"))
      (node (ref "PCIR-7") (pin "2") (pinfunction "2_2") (pintype "passive"))
    )
    (net (code "72") (name "PCI-8") (class "Default")
      (node (ref "PC-HL") (pin "15") (pinfunction "A_15") (pintype "input"))
      (node (ref "PC-I-H") (pin "2") (pinfunction "1Q_2") (pintype "output"))
      (node (ref "PCIR-8") (pin "2") (pinfunction "2_2") (pintype "passive"))
    )
    (net (code "73") (name "PCI-9") (class "Default")
      (node (ref "PC-HL") (pin "1") (pinfunction "B_1") (pintype "input"))
      (node (ref "PC-I-H") (pin "5") (pinfunction "2Q_5") (pintype "output"))
      (node (ref "PCIR-9") (pin "2") (pinfunction "2_2") (pintype "passive"))
    )
    (net (code "74") (name "PCI-10") (class "Default")
      (node (ref "PC-HL") (pin "10") (pinfunction "C_10") (pintype "input"))
      (node (ref "PC-I-H") (pin "6") (pinfunction "3Q_6") (pintype "output"))
      (node (ref "PCIR-10") (pin "2") (pinfunction "2_2") (pintype "passive"))
    )
    (net (code "75") (name "PCI-11") (class "Default")
      (node (ref "PC-HL") (pin "9") (pinfunction "D_9") (pintype "input"))
      (node (ref "PC-I-H") (pin "9") (pinfunction "4Q_9") (pintype "output"))
      (node (ref "PCIR-11") (pin "2") (pinfunction "2_2") (pintype "passive"))
    )
    (net (code "76") (name "PCI-12") (class "Default")
      (node (ref "PC-HH") (pin "15") (pinfunction "A_15") (pintype "input"))
      (node (ref "PC-I-H") (pin "12") (pinfunction "5Q_12") (pintype "output"))
      (node (ref "PCIR-12") (pin "2") (pinfunction "2_2") (pintype "passive"))
    )
    (net (code "77") (name "PCI-H-CP") (class "Default")
      (node (ref "JP1") (pin "1") (pinfunction "1_1") (pintype "passive"))
      (node (ref "PC-I-H") (pin "11") (pinfunction "CLK_11") (pintype "input"))
    )
    (net (code "78") (name "PCI-L-CP") (class "Default")
      (node (ref "JP1") (pin "2") (pinfunction "2_2") (pintype "passive"))
      (node (ref "PC-I-L") (pin "11") (pinfunction "CLK_11") (pintype "input"))
    )
    (net (code "79") (name "ROM-OE") (class "Default")
      (node (ref "JP1") (pin "8") (pinfunction "8_8") (pintype "passive"))
      (node (ref "ROM") (pin "20") (pinfunction "~{CE}_20") (pintype "input"))
      (node (ref "ROM") (pin "22") (pinfunction "~{OE}_22") (pintype "input"))
    )
    (net (code "80") (name "VCC") (class "Default")
      (node (ref "C1") (pin "+") (pinfunction "+_+") (pintype "passive"))
      (node (ref "C2") (pin "+") (pinfunction "+_+") (pintype "passive"))
      (node (ref "C3") (pin "+") (pinfunction "+_+") (pintype "passive"))
      (node (ref "C4") (pin "+") (pinfunction "+_+") (pintype "passive"))
      (node (ref "C5") (pin "+") (pinfunction "+_+") (pintype "passive"))
      (node (ref "C6") (pin "+") (pinfunction "+_+") (pintype "passive"))
      (node (ref "C7") (pin "+") (pinfunction "+_+") (pintype "passive"))
      (node (ref "C8") (pin "+") (pinfunction "+_+") (pintype "passive"))
      (node (ref "JP3") (pin "2") (pinfunction "2_2") (pintype "passive"))
      (node (ref "PC-HH") (pin "16") (pinfunction "+UB_16") (pintype "power_in"))
      (node (ref "PC-HH") (pin "4") (pinfunction "DOWN_4") (pintype "input"))
      (node (ref "PC-HL") (pin "16") (pinfunction "+UB_16") (pintype "power_in"))
      (node (ref "PC-HL") (pin "4") (pinfunction "DOWN_4") (pintype "input"))
      (node (ref "PC-I-H") (pin "1") (pinfunction "~{CLR}_1") (pintype "input"))
      (node (ref "PC-I-H") (pin "20") (pinfunction "+UB_20") (pintype "power_in"))
      (node (ref "PC-I-L") (pin "1") (pinfunction "~{CLR}_1") (pintype "input"))
      (node (ref "PC-I-L") (pin "20") (pinfunction "+UB_20") (pintype "power_in"))
      (node (ref "PC-LH") (pin "16") (pinfunction "+UB_16") (pintype "power_in"))
      (node (ref "PC-LH") (pin "4") (pinfunction "DOWN_4") (pintype "input"))
      (node (ref "PC-LL") (pin "16") (pinfunction "+UB_16") (pintype "power_in"))
      (node (ref "PC-LL") (pin "4") (pinfunction "DOWN_4") (pintype "input"))
      (node (ref "PC-O-H") (pin "20") (pinfunction "+UB_20") (pintype "power_in"))
      (node (ref "PC-O-L") (pin "20") (pinfunction "+UB_20") (pintype "power_in"))
      (node (ref "ROM") (pin "27") (pinfunction "~{WE}_27") (pintype "input"))
      (node (ref "ROM") (pin "28") (pinfunction "VCC_28") (pintype "power_in"))
    )
    (net (code "81") (name "unconnected-(JP1-Pad7)") (class "Default")
      (node (ref "JP1") (pin "7") (pinfunction "7_7") (pintype "passive"))
    )
    (net (code "82") (name "unconnected-(PC-HHC-B-Pad1)") (class "Default")
      (node (ref "PC-HH") (pin "1") (pinfunction "B_1") (pintype "input"))
    )
    (net (code "83") (name "unconnected-(PC-HHC-C-Pad10)") (class "Default")
      (node (ref "PC-HH") (pin "10") (pinfunction "C_10") (pintype "input"))
    )
    (net (code "84") (name "unconnected-(PC-HHC-D-Pad9)") (class "Default")
      (node (ref "PC-HH") (pin "9") (pinfunction "D_9") (pintype "input"))
    )
    (net (code "85") (name "unconnected-(PC-HHC-QB-Pad2)") (class "Default")
      (node (ref "PC-HH") (pin "2") (pinfunction "QB_2") (pintype "output"))
    )
    (net (code "86") (name "unconnected-(PC-HHC-QC-Pad6)") (class "Default")
      (node (ref "PC-HH") (pin "6") (pinfunction "QC_6") (pintype "output"))
    )
    (net (code "87") (name "unconnected-(PC-HHC-QD-Pad7)") (class "Default")
      (node (ref "PC-HH") (pin "7") (pinfunction "QD_7") (pintype "output"))
    )
    (net (code "88") (name "unconnected-(PC-HHC-~{BO}-Pad13)") (class "Default")
      (node (ref "PC-HH") (pin "13") (pinfunction "~{BO}_13") (pintype "output"))
    )
    (net (code "89") (name "unconnected-(PC-HHC-~{CO}-Pad12)") (class "Default")
      (node (ref "PC-HH") (pin "12") (pinfunction "~{CO}_12") (pintype "output"))
    )
    (net (code "90") (name "unconnected-(PC-HLC-~{BO}-Pad13)") (class "Default")
      (node (ref "PC-HL") (pin "13") (pinfunction "~{BO}_13") (pintype "output"))
    )
    (net (code "91") (name "unconnected-(PC-I-HC-6D-Pad14)") (class "Default")
      (node (ref "PC-I-H") (pin "14") (pinfunction "6D_14") (pintype "input"))
    )
    (net (code "92") (name "unconnected-(PC-I-HC-6Q-Pad15)") (class "Default")
      (node (ref "PC-I-H") (pin "15") (pinfunction "6Q_15") (pintype "output"))
    )
    (net (code "93") (name "unconnected-(PC-I-HC-7D-Pad17)") (class "Default")
      (node (ref "PC-I-H") (pin "17") (pinfunction "7D_17") (pintype "input"))
    )
    (net (code "94") (name "unconnected-(PC-I-HC-7Q-Pad16)") (class "Default")
      (node (ref "PC-I-H") (pin "16") (pinfunction "7Q_16") (pintype "output"))
    )
    (net (code "95") (name "unconnected-(PC-I-HC-8D-Pad18)") (class "Default")
      (node (ref "PC-I-H") (pin "18") (pinfunction "8D_18") (pintype "input"))
    )
    (net (code "96") (name "unconnected-(PC-I-HC-8Q-Pad19)") (class "Default")
      (node (ref "PC-I-H") (pin "19") (pinfunction "8Q_19") (pintype "output"))
    )
    (net (code "97") (name "unconnected-(PC-LHC-~{BO}-Pad13)") (class "Default")
      (node (ref "PC-LH") (pin "13") (pinfunction "~{BO}_13") (pintype "output"))
    )
    (net (code "98") (name "unconnected-(PC-LLC-~{BO}-Pad13)") (class "Default")
      (node (ref "PC-LL") (pin "13") (pinfunction "~{BO}_13") (pintype "output"))
    )
    (net (code "99") (name "unconnected-(PC-O-HC-A6-Pad7)") (class "Default")
      (node (ref "PC-O-H") (pin "7") (pinfunction "A6_7") (pintype "bidirectional"))
    )
    (net (code "100") (name "unconnected-(PC-O-HC-A7-Pad8)") (class "Default")
      (node (ref "PC-O-H") (pin "8") (pinfunction "A7_8") (pintype "bidirectional"))
    )
    (net (code "101") (name "unconnected-(PC-O-HC-A8-Pad9)") (class "Default")
      (node (ref "PC-O-H") (pin "9") (pinfunction "A8_9") (pintype "bidirectional"))
    )
    (net (code "102") (name "unconnected-(PC-O-HC-B6-Pad13)") (class "Default")
      (node (ref "PC-O-H") (pin "13") (pinfunction "B6_13") (pintype "bidirectional"))
    )
    (net (code "103") (name "unconnected-(PC-O-HC-B7-Pad12)") (class "Default")
      (node (ref "PC-O-H") (pin "12") (pinfunction "B7_12") (pintype "bidirectional"))
    )
    (net (code "104") (name "unconnected-(PC-O-HC-B8-Pad11)") (class "Default")
      (node (ref "PC-O-H") (pin "11") (pinfunction "B8_11") (pintype "bidirectional"))
    )
    (net (code "105") (name "unconnected-(ROM-NC-Pad1)") (class "Default")
      (node (ref "ROM") (pin "1") (pinfunction "NC_1") (pintype "no_connect"))
    )
    (net (code "106") (name "unconnected-(ROM-NC-Pad26)") (class "Default")
      (node (ref "ROM") (pin "26") (pinfunction "NC_26") (pintype "no_connect"))
    )
  )
)
